# FilterSchematic_REV3.net
KiCad netlist of a schematic drawn in EAGLE
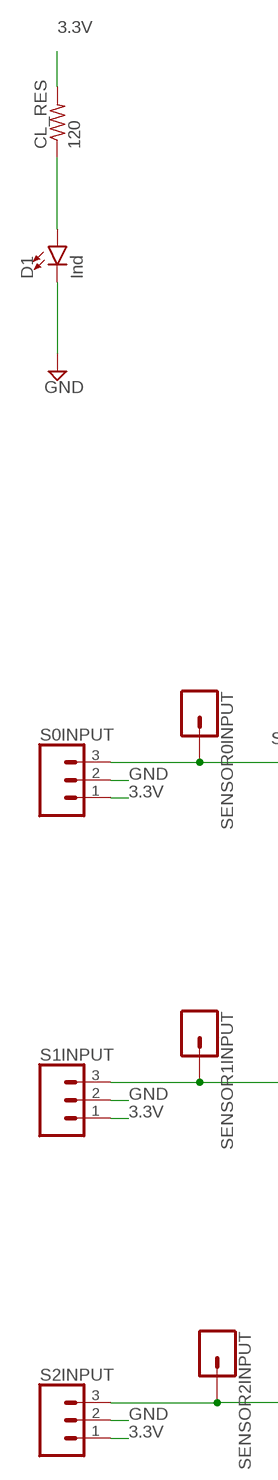
[diagram p0: schematic, sheet 1, part 1 of 2]
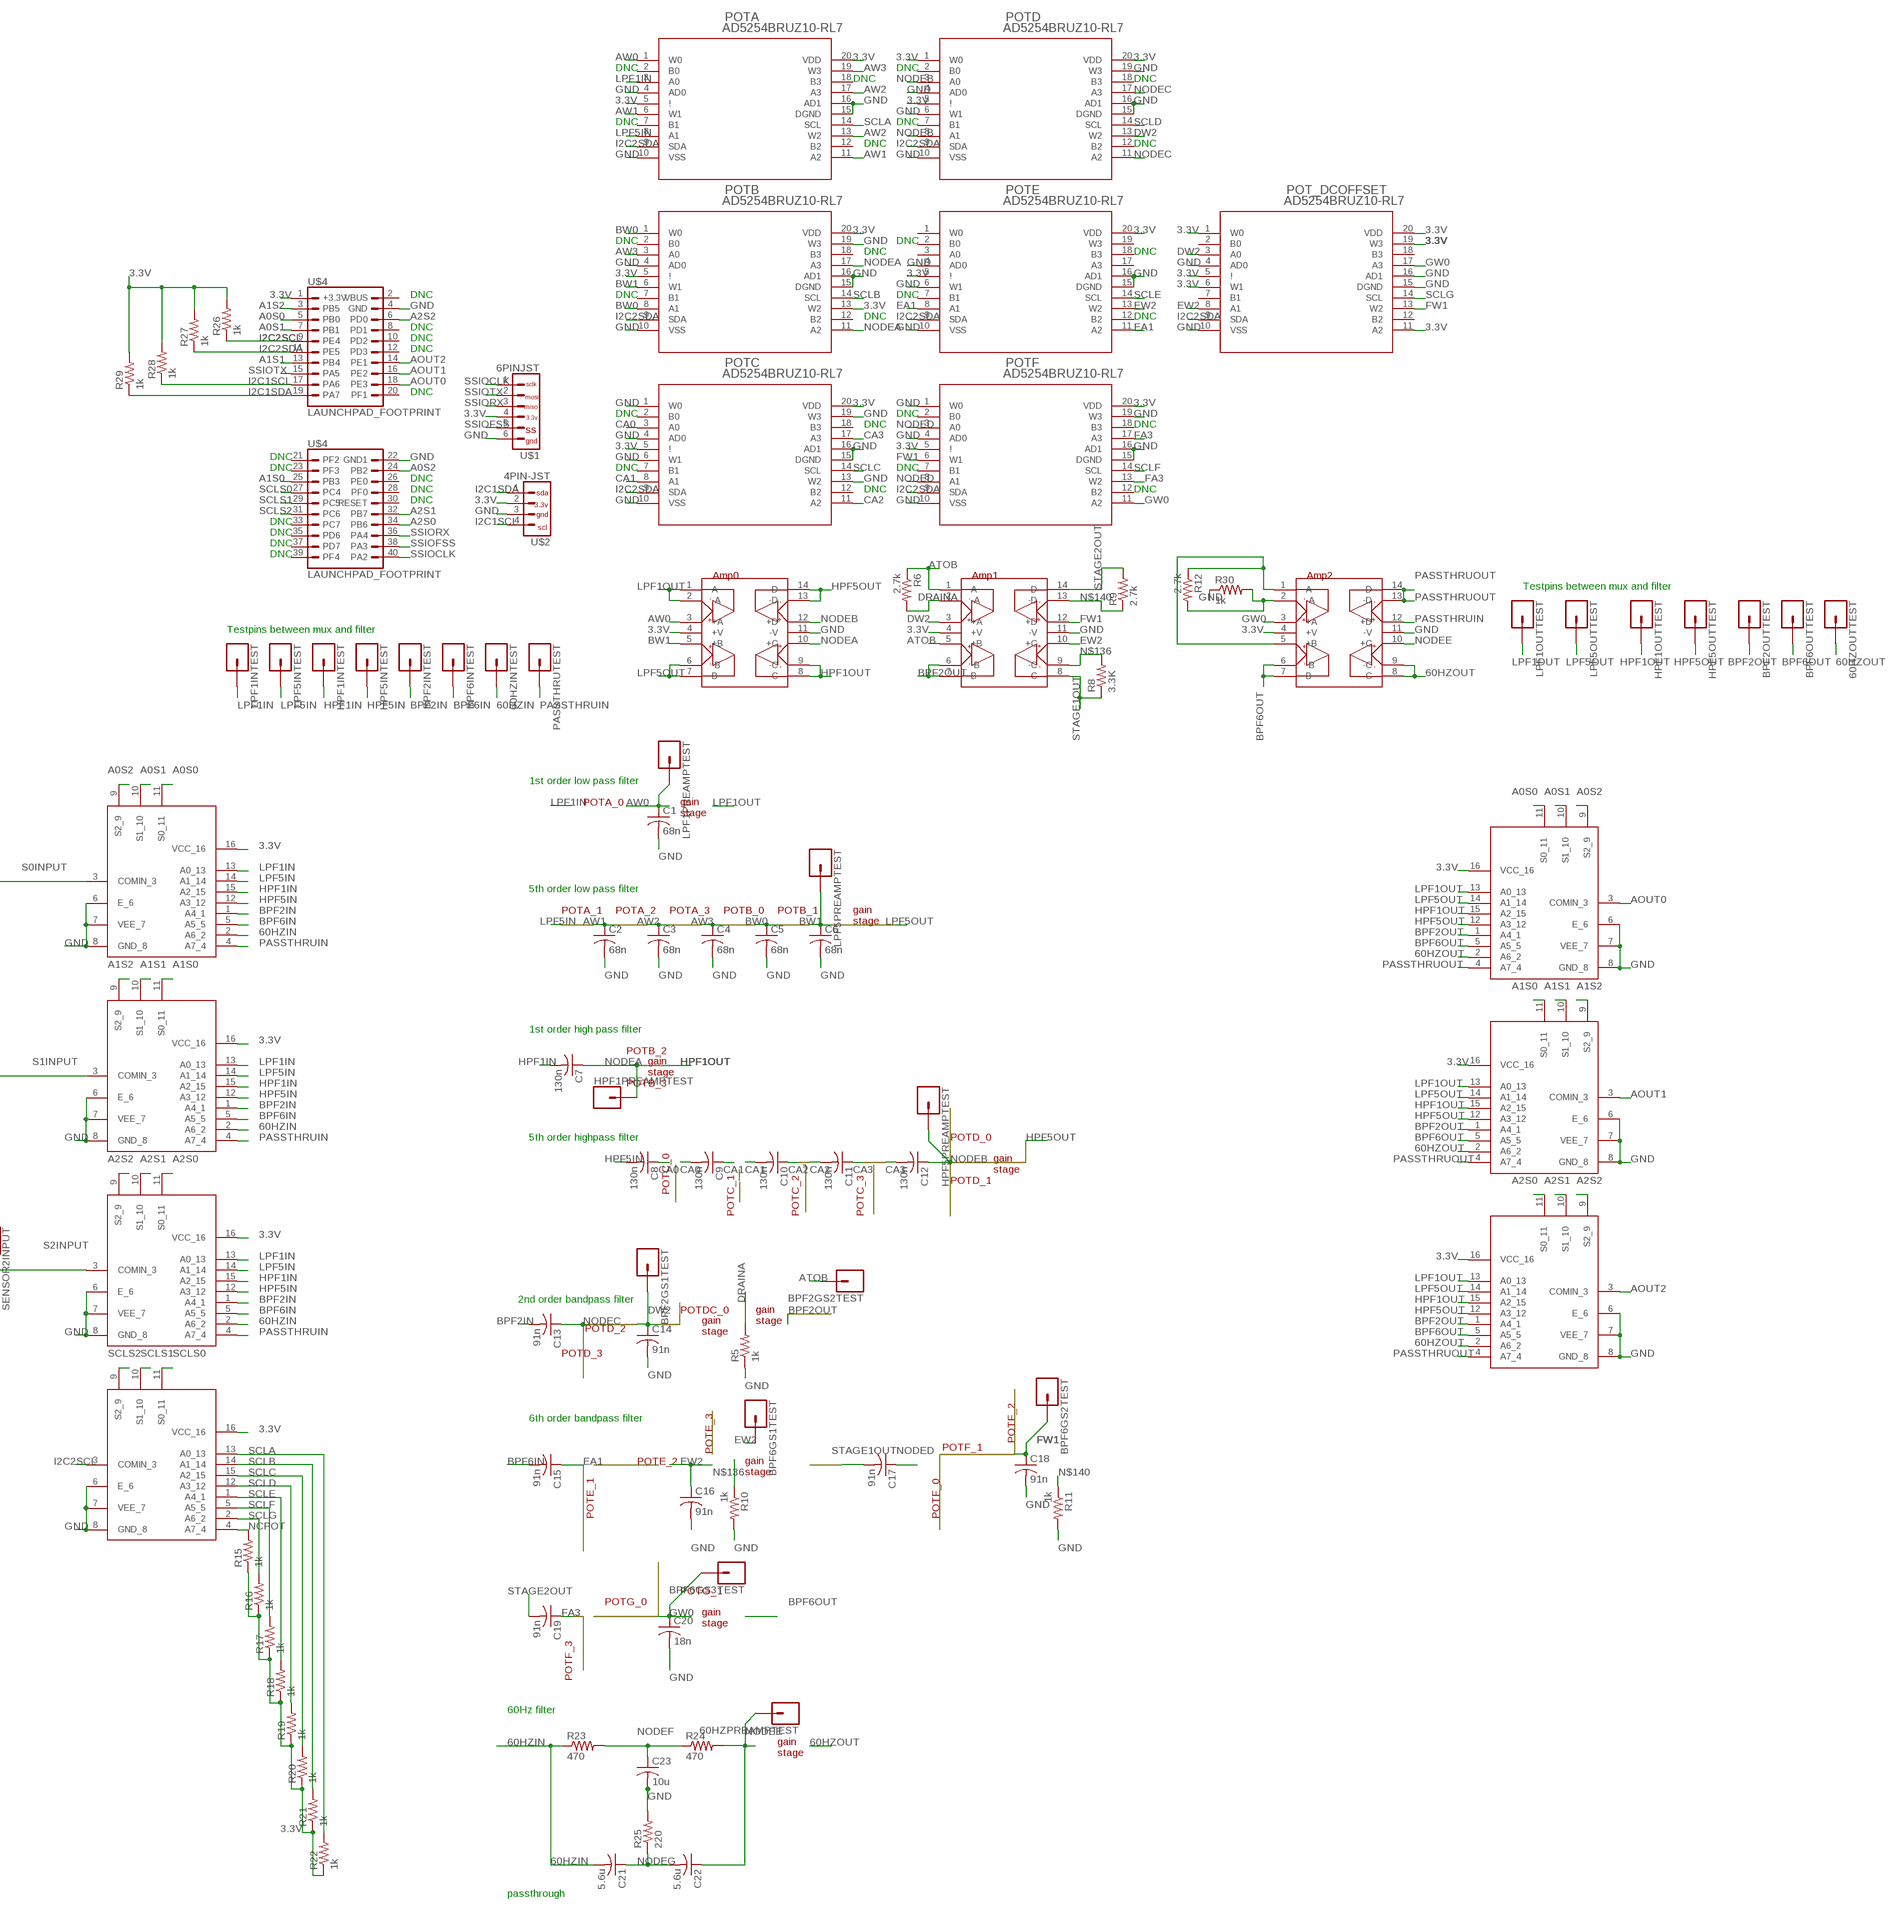
[diagram p1: schematic, sheet 1, part 2 of 2]

(export (version "E")
  (design (tool "Eeschema 10.0.6"))
  (components
    (comp (ref "60HZINTEST")
      (value "CONN_01")
      (footprint "eagle-import:1X01")
      (libsource (lib "eagle-import") (part "CONN_01"))
    )
    (comp (ref "60HZOUTTEST")
      (value "CONN_01")
      (footprint "eagle-import:1X01")
      (libsource (lib "eagle-import") (part "CONN_01"))
    )
    (comp (ref "60HZPREAMPTEST")
      (value "CONN_01")
      (footprint "eagle-import:1X01")
      (libsource (lib "eagle-import") (part "CONN_01"))
    )
    (comp (ref "A2IDEMUX")
      (value "CD74HC4051-Q1")
      (footprint "eagle-import:TSSOP16")
      (libsource (lib "eagle-import") (part "CD74HC4051-Q1"))
    )
    (comp (ref "AI0DEMUX")
      (value "CD74HC4051-Q1")
      (footprint "eagle-import:TSSOP16")
      (libsource (lib "eagle-import") (part "CD74HC4051-Q1"))
    )
    (comp (ref "AI1DEMUX")
      (value "CD74HC4051-Q1")
      (footprint "eagle-import:TSSOP16")
      (libsource (lib "eagle-import") (part "CD74HC4051-Q1"))
    )
    (comp (ref "AMP0")
      (value "OPA4830")
      (footprint "eagle-import:TSSOP14")
      (libsource (lib "eagle-import") (part "OPA4830"))
    )
    (comp (ref "AMP1")
      (value "OPA4830")
      (footprint "eagle-import:TSSOP14")
      (libsource (lib "eagle-import") (part "OPA4830"))
    )
    (comp (ref "AMP2")
      (value "OPA4830")
      (footprint "eagle-import:TSSOP14")
      (libsource (lib "eagle-import") (part "OPA4830"))
    )
    (comp (ref "AO0MUX")
      (value "CD74HC4051-Q1")
      (footprint "eagle-import:TSSOP16")
      (libsource (lib "eagle-import") (part "CD74HC4051-Q1"))
    )
    (comp (ref "AO1MUX")
      (value "CD74HC4051-Q1")
      (footprint "eagle-import:TSSOP16")
      (libsource (lib "eagle-import") (part "CD74HC4051-Q1"))
    )
    (comp (ref "AO2MUX")
      (value "CD74HC4051-Q1")
      (footprint "eagle-import:TSSOP16")
      (libsource (lib "eagle-import") (part "CD74HC4051-Q1"))
    )
    (comp (ref "BPF2GS1TEST")
      (value "CONN_01")
      (footprint "eagle-import:1X01")
      (libsource (lib "eagle-import") (part "CONN_01"))
    )
    (comp (ref "BPF2GS2TEST")
      (value "CONN_01")
      (footprint "eagle-import:1X01")
      (libsource (lib "eagle-import") (part "CONN_01"))
    )
    (comp (ref "BPF2INTEST")
      (value "CONN_01")
      (footprint "eagle-import:1X01")
      (libsource (lib "eagle-import") (part "CONN_01"))
    )
    (comp (ref "BPF2OUTTEST")
      (value "CONN_01")
      (footprint "eagle-import:1X01")
      (libsource (lib "eagle-import") (part "CONN_01"))
    )
    (comp (ref "BPF6GS1TEST")
      (value "CONN_01")
      (footprint "eagle-import:1X01")
      (libsource (lib "eagle-import") (part "CONN_01"))
    )
    (comp (ref "BPF6GS2TEST")
      (value "CONN_01")
      (footprint "eagle-import:1X01")
      (libsource (lib "eagle-import") (part "CONN_01"))
    )
    (comp (ref "BPF6GS3TEST")
      (value "CONN_01")
      (footprint "eagle-import:1X01")
      (libsource (lib "eagle-import") (part "CONN_01"))
    )
    (comp (ref "BPF6INTEST")
      (value "CONN_01")
      (footprint "eagle-import:1X01")
      (libsource (lib "eagle-import") (part "CONN_01"))
    )
    (comp (ref "BPF6OUTTEST")
      (value "CONN_01")
      (footprint "eagle-import:1X01")
      (libsource (lib "eagle-import") (part "CONN_01"))
    )
    (comp (ref "C1")
      (value "68n")
      (footprint "eagle-import:C0805")
      (libsource (lib "eagle-import") (part "C-USC0805"))
    )
    (comp (ref "C2")
      (value "68n")
      (footprint "eagle-import:C0805")
      (libsource (lib "eagle-import") (part "C-USC0805"))
    )
    (comp (ref "C3")
      (value "68n")
      (footprint "eagle-import:C0805")
      (libsource (lib "eagle-import") (part "C-USC0805"))
    )
    (comp (ref "C4")
      (value "68n")
      (footprint "eagle-import:C0805")
      (libsource (lib "eagle-import") (part "C-USC0805"))
    )
    (comp (ref "C5")
      (value "68n")
      (footprint "eagle-import:C0805")
      (libsource (lib "eagle-import") (part "C-USC0805"))
    )
    (comp (ref "C6")
      (value "68n")
      (footprint "eagle-import:C0805")
      (libsource (lib "eagle-import") (part "C-USC0805"))
    )
    (comp (ref "C7")
      (value "130n")
      (footprint "eagle-import:C0805")
      (libsource (lib "eagle-import") (part "C-USC0805"))
    )
    (comp (ref "C8")
      (value "130n")
      (footprint "eagle-import:C0805")
      (libsource (lib "eagle-import") (part "C-USC0805"))
    )
    (comp (ref "C9")
      (value "130n")
      (footprint "eagle-import:C0805")
      (libsource (lib "eagle-import") (part "C-USC0805"))
    )
    (comp (ref "C10")
      (value "130n")
      (footprint "eagle-import:C0805")
      (libsource (lib "eagle-import") (part "C-USC0805"))
    )
    (comp (ref "C11")
      (value "130n")
      (footprint "eagle-import:C0805")
      (libsource (lib "eagle-import") (part "C-USC0805"))
    )
    (comp (ref "C12")
      (value "130n")
      (footprint "eagle-import:C0805")
      (libsource (lib "eagle-import") (part "C-USC0805"))
    )
    (comp (ref "C13")
      (value "91n")
      (footprint "eagle-import:C0805")
      (libsource (lib "eagle-import") (part "C-USC0805"))
    )
    (comp (ref "C14")
      (value "91n")
      (footprint "eagle-import:C0805")
      (libsource (lib "eagle-import") (part "C-USC0805"))
    )
    (comp (ref "C15")
      (value "91n")
      (footprint "eagle-import:C0805")
      (libsource (lib "eagle-import") (part "C-USC0805"))
    )
    (comp (ref "C16")
      (value "91n")
      (footprint "eagle-import:C0805")
      (libsource (lib "eagle-import") (part "C-USC0805"))
    )
    (comp (ref "C17")
      (value "91n")
      (footprint "eagle-import:C0805")
      (libsource (lib "eagle-import") (part "C-USC0805"))
    )
    (comp (ref "C18")
      (value "91n")
      (footprint "eagle-import:C0805")
      (libsource (lib "eagle-import") (part "C-USC0805"))
    )
    (comp (ref "C19")
      (value "91n")
      (footprint "eagle-import:C0805")
      (libsource (lib "eagle-import") (part "C-USC0805"))
    )
    (comp (ref "C20")
      (value "18n")
      (footprint "eagle-import:C0805")
      (libsource (lib "eagle-import") (part "C-USC0805"))
    )
    (comp (ref "C21")
      (value "5.6u")
      (footprint "eagle-import:C0805")
      (libsource (lib "eagle-import") (part "C-USC0805"))
    )
    (comp (ref "C22")
      (value "5.6u")
      (footprint "eagle-import:C0805")
      (libsource (lib "eagle-import") (part "C-USC0805"))
    )
    (comp (ref "C23")
      (value "10u")
      (footprint "eagle-import:C0805")
      (libsource (lib "eagle-import") (part "C-USC0805"))
    )
    (comp (ref "CL_RES")
      (value "120")
      (footprint "eagle-import:R0805")
      (libsource (lib "eagle-import") (part "rcl_334_R-US_R0805"))
    )
    (comp (ref "D1")
      (value "Ind")
      (footprint "eagle-import:LED-0603")
      (libsource (lib "eagle-import") (part "LED-GREEN0603"))
    )
    (comp (ref "HPF1INTEST")
      (value "CONN_01")
      (footprint "eagle-import:1X01")
      (libsource (lib "eagle-import") (part "CONN_01"))
    )
    (comp (ref "HPF1OUTTEST")
      (value "CONN_01")
      (footprint "eagle-import:1X01")
      (libsource (lib "eagle-import") (part "CONN_01"))
    )
    (comp (ref "HPF1PREAMPTEST")
      (value "CONN_01")
      (footprint "eagle-import:1X01")
      (libsource (lib "eagle-import") (part "CONN_01"))
    )
    (comp (ref "HPF5INTEST")
      (value "CONN_01")
      (footprint "eagle-import:1X01")
      (libsource (lib "eagle-import") (part "CONN_01"))
    )
    (comp (ref "HPF5OUTTEST")
      (value "CONN_01")
      (footprint "eagle-import:1X01")
      (libsource (lib "eagle-import") (part "CONN_01"))
    )
    (comp (ref "HPF5PREAMPTEST")
      (value "CONN_01")
      (footprint "eagle-import:1X01")
      (libsource (lib "eagle-import") (part "CONN_01"))
    )
    (comp (ref "LPF1INTEST")
      (value "CONN_01")
      (footprint "eagle-import:1X01")
      (libsource (lib "eagle-import") (part "CONN_01"))
    )
    (comp (ref "LPF1OUTTEST")
      (value "CONN_01")
      (footprint "eagle-import:1X01")
      (libsource (lib "eagle-import") (part "CONN_01"))
    )
    (comp (ref "LPF1PREAMPTEST")
      (value "CONN_01")
      (footprint "eagle-import:1X01")
      (libsource (lib "eagle-import") (part "CONN_01"))
    )
    (comp (ref "LPF5INTEST")
      (value "CONN_01")
      (footprint "eagle-import:1X01")
      (libsource (lib "eagle-import") (part "CONN_01"))
    )
    (comp (ref "LPF5OUTTEST")
      (value "CONN_01")
      (footprint "eagle-import:1X01")
      (libsource (lib "eagle-import") (part "CONN_01"))
    )
    (comp (ref "LPF5PREAMPTEST")
      (value "CONN_01")
      (footprint "eagle-import:1X01")
      (libsource (lib "eagle-import") (part "CONN_01"))
    )
    (comp (ref "PASSTHRUTEST")
      (value "CONN_01")
      (footprint "eagle-import:1X01")
      (libsource (lib "eagle-import") (part "CONN_01"))
    )
    (comp (ref "POTA")
      (value "AD5254BRUZ10-RL7")
      (footprint "eagle-import:RU_20")
      (fields (field (name "MANUFACTURER_PART_NUMBER") "AD5254BRUZ10RL7"))
      (libsource (lib "eagle-import") (part "AD5254BRUZ10-RL7"))
    )
    (comp (ref "POTB")
      (value "AD5254BRUZ10-RL7")
      (footprint "eagle-import:RU_20")
      (fields (field (name "MANUFACTURER_PART_NUMBER") "AD5254BRUZ10RL7"))
      (libsource (lib "eagle-import") (part "AD5254BRUZ10-RL7"))
    )
    (comp (ref "POTC")
      (value "AD5254BRUZ10-RL7")
      (footprint "eagle-import:RU_20")
      (fields (field (name "MANUFACTURER_PART_NUMBER") "AD5254BRUZ10RL7"))
      (libsource (lib "eagle-import") (part "AD5254BRUZ10-RL7"))
    )
    (comp (ref "POTD")
      (value "AD5254BRUZ10-RL7")
      (footprint "eagle-import:RU_20")
      (fields (field (name "MANUFACTURER_PART_NUMBER") "AD5254BRUZ10RL7"))
      (libsource (lib "eagle-import") (part "AD5254BRUZ10-RL7"))
    )
    (comp (ref "POTE")
      (value "AD5254BRUZ10-RL7")
      (footprint "eagle-import:RU_20")
      (fields (field (name "MANUFACTURER_PART_NUMBER") "AD5254BRUZ10RL7"))
      (libsource (lib "eagle-import") (part "AD5254BRUZ10-RL7"))
    )
    (comp (ref "POTF")
      (value "AD5254BRUZ10-RL7")
      (footprint "eagle-import:RU_20")
      (fields (field (name "MANUFACTURER_PART_NUMBER") "AD5254BRUZ10RL7"))
      (libsource (lib "eagle-import") (part "AD5254BRUZ10-RL7"))
    )
    (comp (ref "POT_DCOFFSET")
      (value "AD5254BRUZ10-RL7")
      (footprint "eagle-import:RU_20")
      (fields (field (name "MANUFACTURER_PART_NUMBER") "AD5254BRUZ10RL7"))
      (libsource (lib "eagle-import") (part "AD5254BRUZ10-RL7"))
    )
    (comp (ref "R5")
      (value "1k")
      (footprint "eagle-import:R0805")
      (libsource (lib "eagle-import") (part "rcl_334_R-US_R0805"))
    )
    (comp (ref "R6")
      (value "2.7k")
      (footprint "eagle-import:R0805")
      (libsource (lib "eagle-import") (part "rcl_334_R-US_R0805"))
    )
    (comp (ref "R8")
      (value "3.3K")
      (footprint "eagle-import:R0805")
      (libsource (lib "eagle-import") (part "rcl_334_R-US_R0805"))
    )
    (comp (ref "R9")
      (value "2.7k")
      (footprint "eagle-import:R0805")
      (libsource (lib "eagle-import") (part "rcl_334_R-US_R0805"))
    )
    (comp (ref "R10")
      (value "1k")
      (footprint "eagle-import:R0805")
      (libsource (lib "eagle-import") (part "rcl_334_R-US_R0805"))
    )
    (comp (ref "R11")
      (value "1k")
      (footprint "eagle-import:R0805")
      (libsource (lib "eagle-import") (part "rcl_334_R-US_R0805"))
    )
    (comp (ref "R12")
      (value "2.7k")
      (footprint "eagle-import:R0805")
      (libsource (lib "eagle-import") (part "rcl_334_R-US_R0805"))
    )
    (comp (ref "R15")
      (value "1k")
      (footprint "eagle-import:R0805")
      (libsource (lib "eagle-import") (part "rcl_334_R-US_R0805"))
    )
    (comp (ref "R16")
      (value "1k")
      (footprint "eagle-import:R0805")
      (libsource (lib "eagle-import") (part "rcl_334_R-US_R0805"))
    )
    (comp (ref "R17")
      (value "1k")
      (footprint "eagle-import:R0805")
      (libsource (lib "eagle-import") (part "rcl_334_R-US_R0805"))
    )
    (comp (ref "R18")
      (value "1k")
      (footprint "eagle-import:R0805")
      (libsource (lib "eagle-import") (part "rcl_334_R-US_R0805"))
    )
    (comp (ref "R19")
      (value "1k")
      (footprint "eagle-import:R0805")
      (libsource (lib "eagle-import") (part "rcl_334_R-US_R0805"))
    )
    (comp (ref "R20")
      (value "1k")
      (footprint "eagle-import:R0805")
      (libsource (lib "eagle-import") (part "rcl_334_R-US_R0805"))
    )
    (comp (ref "R21")
      (value "1k")
      (footprint "eagle-import:R0805")
      (libsource (lib "eagle-import") (part "rcl_334_R-US_R0805"))
    )
    (comp (ref "R22")
      (value "1k")
      (footprint "eagle-import:R0805")
      (libsource (lib "eagle-import") (part "rcl_334_R-US_R0805"))
    )
    (comp (ref "R23")
      (value "470")
      (footprint "eagle-import:R0805")
      (libsource (lib "eagle-import") (part "R-US_R0805"))
    )
    (comp (ref "R24")
      (value "470")
      (footprint "eagle-import:R0805")
      (libsource (lib "eagle-import") (part "R-US_R0805"))
    )
    (comp (ref "R25")
      (value "220")
      (footprint "eagle-import:R0805")
      (libsource (lib "eagle-import") (part "R-US_R0805"))
    )
    (comp (ref "R26")
      (value "1k")
      (footprint "eagle-import:R0805")
      (libsource (lib "eagle-import") (part "rcl_334_R-US_R0805"))
    )
    (comp (ref "R27")
      (value "1k")
      (footprint "eagle-import:R0805")
      (libsource (lib "eagle-import") (part "rcl_334_R-US_R0805"))
    )
    (comp (ref "R28")
      (value "1k")
      (footprint "eagle-import:R0805")
      (libsource (lib "eagle-import") (part "rcl_334_R-US_R0805"))
    )
    (comp (ref "R29")
      (value "1k")
      (footprint "eagle-import:R0805")
      (libsource (lib "eagle-import") (part "rcl_334_R-US_R0805"))
    )
    (comp (ref "R30")
      (value "1k")
      (footprint "eagle-import:R0805")
      (libsource (lib "eagle-import") (part "rcl_334_R-US_R0805"))
    )
    (comp (ref "S0INPUT")
      (value "CONN_03JST-PTH-VERT")
      (footprint "eagle-import:JST-3-PTH-VERT")
      (libsource (lib "eagle-import") (part "CONN_03JST-PTH-VERT"))
    )
    (comp (ref "S1INPUT")
      (value "CONN_03JST-PTH-VERT")
      (footprint "eagle-import:JST-3-PTH-VERT")
      (libsource (lib "eagle-import") (part "CONN_03JST-PTH-VERT"))
    )
    (comp (ref "S2INPUT")
      (value "CONN_03JST-PTH-VERT")
      (footprint "eagle-import:JST-3-PTH-VERT")
      (libsource (lib "eagle-import") (part "CONN_03JST-PTH-VERT"))
    )
    (comp (ref "SCLMUX")
      (value "CD74HC4051-Q1")
      (footprint "eagle-import:TSSOP16")
      (libsource (lib "eagle-import") (part "CD74HC4051-Q1"))
    )
    (comp (ref "SENSOR0INPUT")
      (value "CONN_01")
      (footprint "eagle-import:1X01")
      (libsource (lib "eagle-import") (part "CONN_01"))
    )
    (comp (ref "SENSOR1INPUT")
      (value "CONN_01")
      (footprint "eagle-import:1X01")
      (libsource (lib "eagle-import") (part "CONN_01"))
    )
    (comp (ref "SENSOR2INPUT")
      (value "CONN_01")
      (footprint "eagle-import:1X01")
      (libsource (lib "eagle-import") (part "CONN_01"))
    )
    (comp (ref "U$1")
      (value "6PINJST")
      (footprint "eagle-import:JST-6-PTH-VERT")
      (libsource (lib "eagle-import") (part "6PINJST"))
    )
    (comp (ref "U$2")
      (value "4PIN-JST")
      (footprint "eagle-import:JST-4-PTH-VERT")
      (libsource (lib "eagle-import") (part "4PIN-JST"))
    )
    (comp (ref "U$4")
      (value "LAUNCHPAD_FOOTPRINT")
      (footprint "eagle-import:SSW-110-02-S-D")
      (libsource (lib "eagle-import") (part "LAUNCHPAD_FOOTPRINT"))
    )
  )
  (nets
    (net (code "1") (name "/3.3V") (class "Default")
      (node (ref "A2IDEMUX") (pin "16") (pinfunction "VCC_16_16") (pintype "bidirectional"))
      (node (ref "AI0DEMUX") (pin "16") (pinfunction "VCC_16_16") (pintype "bidirectional"))
      (node (ref "AI1DEMUX") (pin "16") (pinfunction "VCC_16_16") (pintype "bidirectional"))
      (node (ref "AMP0") (pin "4") (pinfunction "+V_4") (pintype "bidirectional"))
      (node (ref "AMP1") (pin "4") (pinfunction "+V_4") (pintype "bidirectional"))
      (node (ref "AMP2") (pin "4") (pinfunction "+V_4") (pintype "bidirectional"))
      (node (ref "AO0MUX") (pin "16") (pinfunction "VCC_16_16") (pintype "bidirectional"))
      (node (ref "AO1MUX") (pin "16") (pinfunction "VCC_16_16") (pintype "bidirectional"))
      (node (ref "AO2MUX") (pin "16") (pinfunction "VCC_16_16") (pintype "bidirectional"))
      (node (ref "CL_RES") (pin "2") (pinfunction "2_2") (pintype "passive"))
      (node (ref "POTA") (pin "20") (pinfunction "VDD_20") (pintype "power_in"))
      (node (ref "POTA") (pin "5") (pinfunction "~_5") (pintype "passive"))
      (node (ref "POTB") (pin "13") (pinfunction "W2_13") (pintype "passive"))
      (node (ref "POTB") (pin "20") (pinfunction "VDD_20") (pintype "power_in"))
      (node (ref "POTB") (pin "5") (pinfunction "~_5") (pintype "passive"))
      (node (ref "POTC") (pin "20") (pinfunction "VDD_20") (pintype "power_in"))
      (node (ref "POTC") (pin "5") (pinfunction "~_5") (pintype "passive"))
      (node (ref "POTD") (pin "1") (pinfunction "W0_1") (pintype "passive"))
      (node (ref "POTD") (pin "20") (pinfunction "VDD_20") (pintype "power_in"))
      (node (ref "POTD") (pin "5") (pinfunction "~_5") (pintype "passive"))
      (node (ref "POTE") (pin "20") (pinfunction "VDD_20") (pintype "power_in"))
      (node (ref "POTE") (pin "5") (pinfunction "~_5") (pintype "passive"))
      (node (ref "POTF") (pin "20") (pinfunction "VDD_20") (pintype "power_in"))
      (node (ref "POTF") (pin "5") (pinfunction "~_5") (pintype "passive"))
      (node (ref "POT_DCOFFSET") (pin "1") (pinfunction "W0_1") (pintype "passive"))
      (node (ref "POT_DCOFFSET") (pin "11") (pinfunction "A2_11") (pintype "passive"))
      (node (ref "POT_DCOFFSET") (pin "19") (pinfunction "W3_19") (pintype "passive"))
      (node (ref "POT_DCOFFSET") (pin "20") (pinfunction "VDD_20") (pintype "power_in"))
      (node (ref "POT_DCOFFSET") (pin "5") (pinfunction "~_5") (pintype "passive"))
      (node (ref "POT_DCOFFSET") (pin "6") (pinfunction "W1_6") (pintype "passive"))
      (node (ref "R15") (pin "1") (pinfunction "1_1") (pintype "passive"))
      (node (ref "R16") (pin "1") (pinfunction "1_1") (pintype "passive"))
      (node (ref "R17") (pin "1") (pinfunction "1_1") (pintype "passive"))
      (node (ref "R18") (pin "1") (pinfunction "1_1") (pintype "passive"))
      (node (ref "R19") (pin "1") (pinfunction "1_1") (pintype "passive"))
      (node (ref "R20") (pin "1") (pinfunction "1_1") (pintype "passive"))
      (node (ref "R21") (pin "1") (pinfunction "1_1") (pintype "passive"))
      (node (ref "R22") (pin "1") (pinfunction "1_1") (pintype "passive"))
      (node (ref "R26") (pin "2") (pinfunction "2_2") (pintype "passive"))
      (node (ref "R27") (pin "2") (pinfunction "2_2") (pintype "passive"))
      (node (ref "R28") (pin "2") (pinfunction "2_2") (pintype "passive"))
      (node (ref "R29") (pin "2") (pinfunction "2_2") (pintype "passive"))
      (node (ref "S0INPUT") (pin "1") (pinfunction "1_1") (pintype "passive"))
      (node (ref "S1INPUT") (pin "1") (pinfunction "1_1") (pintype "passive"))
      (node (ref "S2INPUT") (pin "1") (pinfunction "1_1") (pintype "passive"))
      (node (ref "SCLMUX") (pin "16") (pinfunction "VCC_16_16") (pintype "bidirectional"))
      (node (ref "U$1") (pin "4") (pinfunction "4_4") (pintype "passive"))
      (node (ref "U$2") (pin "2") (pinfunction "2_2") (pintype "passive"))
      (node (ref "U$4") (pin "1") (pinfunction "+3.3V_1") (pintype "passive"))
    )
    (net (code "2") (name "/60HZIN") (class "Default")
      (node (ref "60HZINTEST") (pin "1") (pinfunction "1_1") (pintype "passive"))
      (node (ref "A2IDEMUX") (pin "2") (pinfunction "A6_2_2") (pintype "bidirectional"))
      (node (ref "AI0DEMUX") (pin "2") (pinfunction "A6_2_2") (pintype "bidirectional"))
      (node (ref "AI1DEMUX") (pin "2") (pinfunction "A6_2_2") (pintype "bidirectional"))
      (node (ref "C21") (pin "2") (pinfunction "2_2") (pintype "passive"))
      (node (ref "R23") (pin "1") (pinfunction "1_1") (pintype "passive"))
    )
    (net (code "3") (name "/60HZOUT") (class "Default")
      (node (ref "60HZOUTTEST") (pin "1") (pinfunction "1_1") (pintype "passive"))
      (node (ref "AMP2") (pin "8") (pinfunction "C_8") (pintype "bidirectional"))
      (node (ref "AMP2") (pin "9") (pinfunction "-C_9") (pintype "bidirectional"))
      (node (ref "AO0MUX") (pin "2") (pinfunction "A6_2_2") (pintype "bidirectional"))
      (node (ref "AO1MUX") (pin "2") (pinfunction "A6_2_2") (pintype "bidirectional"))
      (node (ref "AO2MUX") (pin "2") (pinfunction "A6_2_2") (pintype "bidirectional"))
    )
    (net (code "4") (name "/A0S0") (class "Default")
      (node (ref "AI0DEMUX") (pin "11") (pinfunction "S0_11_11") (pintype "bidirectional"))
      (node (ref "AO0MUX") (pin "11") (pinfunction "S0_11_11") (pintype "bidirectional"))
      (node (ref "U$4") (pin "5") (pinfunction "PB0_5") (pintype "passive"))
    )
    (net (code "5") (name "/A0S1") (class "Default")
      (node (ref "AI0DEMUX") (pin "10") (pinfunction "S1_10_10") (pintype "bidirectional"))
      (node (ref "AO0MUX") (pin "10") (pinfunction "S1_10_10") (pintype "bidirectional"))
      (node (ref "U$4") (pin "7") (pinfunction "PB1_7") (pintype "passive"))
    )
    (net (code "6") (name "/A0S2") (class "Default")
      (node (ref "AI0DEMUX") (pin "9") (pinfunction "S2_9_9") (pintype "bidirectional"))
      (node (ref "AO0MUX") (pin "9") (pinfunction "S2_9_9") (pintype "bidirectional"))
      (node (ref "U$4") (pin "24") (pinfunction "PB2_24") (pintype "passive"))
    )
    (net (code "7") (name "/A1S0") (class "Default")
      (node (ref "AI1DEMUX") (pin "11") (pinfunction "S0_11_11") (pintype "bidirectional"))
      (node (ref "AO1MUX") (pin "11") (pinfunction "S0_11_11") (pintype "bidirectional"))
      (node (ref "U$4") (pin "25") (pinfunction "PB3_25") (pintype "passive"))
    )
    (net (code "8") (name "/A1S1") (class "Default")
      (node (ref "AI1DEMUX") (pin "10") (pinfunction "S1_10_10") (pintype "bidirectional"))
      (node (ref "AO1MUX") (pin "10") (pinfunction "S1_10_10") (pintype "bidirectional"))
      (node (ref "U$4") (pin "13") (pinfunction "PB4_13") (pintype "passive"))
    )
    (net (code "9") (name "/A1S2") (class "Default")
      (node (ref "AI1DEMUX") (pin "9") (pinfunction "S2_9_9") (pintype "bidirectional"))
      (node (ref "AO1MUX") (pin "9") (pinfunction "S2_9_9") (pintype "bidirectional"))
      (node (ref "U$4") (pin "3") (pinfunction "PB5_3") (pintype "passive"))
    )
    (net (code "10") (name "/A2S0") (class "Default")
      (node (ref "A2IDEMUX") (pin "11") (pinfunction "S0_11_11") (pintype "bidirectional"))
      (node (ref "AO2MUX") (pin "11") (pinfunction "S0_11_11") (pintype "bidirectional"))
      (node (ref "U$4") (pin "34") (pinfunction "PB6_34") (pintype "passive"))
    )
    (net (code "11") (name "/A2S1") (class "Default")
      (node (ref "A2IDEMUX") (pin "10") (pinfunction "S1_10_10") (pintype "bidirectional"))
      (node (ref "AO2MUX") (pin "10") (pinfunction "S1_10_10") (pintype "bidirectional"))
      (node (ref "U$4") (pin "32") (pinfunction "PB7_32") (pintype "passive"))
    )
    (net (code "12") (name "/A2S2") (class "Default")
      (node (ref "A2IDEMUX") (pin "9") (pinfunction "S2_9_9") (pintype "bidirectional"))
      (node (ref "AO2MUX") (pin "9") (pinfunction "S2_9_9") (pintype "bidirectional"))
      (node (ref "U$4") (pin "6") (pinfunction "PD0_6") (pintype "passive"))
    )
    (net (code "13") (name "/AOUT0") (class "Default")
      (node (ref "AO0MUX") (pin "3") (pinfunction "COMIN_3_3") (pintype "bidirectional"))
      (node (ref "U$4") (pin "18") (pinfunction "PE3_18") (pintype "passive"))
    )
    (net (code "14") (name "/AOUT1") (class "Default")
      (node (ref "AO1MUX") (pin "3") (pinfunction "COMIN_3_3") (pintype "bidirectional"))
      (node (ref "U$4") (pin "16") (pinfunction "PE2_16") (pintype "passive"))
    )
    (net (code "15") (name "/AOUT2") (class "Default")
      (node (ref "AO2MUX") (pin "3") (pinfunction "COMIN_3_3") (pintype "bidirectional"))
      (node (ref "U$4") (pin "14") (pinfunction "PE1_14") (pintype "passive"))
    )
    (net (code "16") (name "/ATOB") (class "Default")
      (node (ref "AMP1") (pin "1") (pinfunction "A_1") (pintype "bidirectional"))
      (node (ref "AMP1") (pin "5") (pinfunction "+B_5") (pintype "bidirectional"))
      (node (ref "BPF2GS2TEST") (pin "1") (pinfunction "1_1") (pintype "passive"))
      (node (ref "R6") (pin "1") (pinfunction "1_1") (pintype "passive"))
    )
    (net (code "17") (name "/AW0") (class "Default")
      (node (ref "AMP0") (pin "3") (pinfunction "+A_3") (pintype "bidirectional"))
      (node (ref "C1") (pin "1") (pinfunction "1_1") (pintype "passive"))
      (node (ref "LPF1PREAMPTEST") (pin "1") (pinfunction "1_1") (pintype "passive"))
      (node (ref "POTA") (pin "1") (pinfunction "W0_1") (pintype "passive"))
    )
    (net (code "18") (name "/AW1") (class "Default")
      (node (ref "C2") (pin "1") (pinfunction "1_1") (pintype "passive"))
      (node (ref "POTA") (pin "11") (pinfunction "A2_11") (pintype "passive"))
      (node (ref "POTA") (pin "6") (pinfunction "W1_6") (pintype "passive"))
    )
    (net (code "19") (name "/AW2") (class "Default")
      (node (ref "C3") (pin "1") (pinfunction "1_1") (pintype "passive"))
      (node (ref "POTA") (pin "13") (pinfunction "W2_13") (pintype "passive"))
      (node (ref "POTA") (pin "17") (pinfunction "A3_17") (pintype "passive"))
    )
    (net (code "20") (name "/AW3") (class "Default")
      (node (ref "C4") (pin "1") (pinfunction "1_1") (pintype "passive"))
      (node (ref "POTA") (pin "19") (pinfunction "W3_19") (pintype "passive"))
      (node (ref "POTB") (pin "3") (pinfunction "A0_3") (pintype "passive"))
    )
    (net (code "21") (name "/BPF2IN") (class "Default")
      (node (ref "A2IDEMUX") (pin "1") (pinfunction "A4_1_1") (pintype "bidirectional"))
      (node (ref "AI0DEMUX") (pin "1") (pinfunction "A4_1_1") (pintype "bidirectional"))
      (node (ref "AI1DEMUX") (pin "1") (pinfunction "A4_1_1") (pintype "bidirectional"))
      (node (ref "BPF2INTEST") (pin "1") (pinfunction "1_1") (pintype "passive"))
      (node (ref "C13") (pin "2") (pinfunction "2_2") (pintype "passive"))
    )
    (net (code "22") (name "/BPF2OUT") (class "Default")
      (node (ref "AMP1") (pin "6") (pinfunction "-B_6") (pintype "bidirectional"))
      (node (ref "AMP1") (pin "7") (pinfunction "B_7") (pintype "bidirectional"))
      (node (ref "AO0MUX") (pin "1") (pinfunction "A4_1_1") (pintype "bidirectional"))
      (node (ref "AO1MUX") (pin "1") (pinfunction "A4_1_1") (pintype "bidirectional"))
      (node (ref "AO2MUX") (pin "1") (pinfunction "A4_1_1") (pintype "bidirectional"))
      (node (ref "BPF2OUTTEST") (pin "1") (pinfunction "1_1") (pintype "passive"))
    )
    (net (code "23") (name "/BPF6IN") (class "Default")
      (node (ref "A2IDEMUX") (pin "5") (pinfunction "A5_5_5") (pintype "bidirectional"))
      (node (ref "AI0DEMUX") (pin "5") (pinfunction "A5_5_5") (pintype "bidirectional"))
      (node (ref "AI1DEMUX") (pin "5") (pinfunction "A5_5_5") (pintype "bidirectional"))
      (node (ref "BPF6INTEST") (pin "1") (pinfunction "1_1") (pintype "passive"))
      (node (ref "C15") (pin "2") (pinfunction "2_2") (pintype "passive"))
    )
    (net (code "24") (name "/BPF6OUT") (class "Default")
      (node (ref "AMP2") (pin "6") (pinfunction "-B_6") (pintype "bidirectional"))
      (node (ref "AMP2") (pin "7") (pinfunction "B_7") (pintype "bidirectional"))
      (node (ref "AO0MUX") (pin "5") (pinfunction "A5_5_5") (pintype "bidirectional"))
      (node (ref "AO1MUX") (pin "5") (pinfunction "A5_5_5") (pintype "bidirectional"))
      (node (ref "AO2MUX") (pin "5") (pinfunction "A5_5_5") (pintype "bidirectional"))
      (node (ref "BPF6OUTTEST") (pin "1") (pinfunction "1_1") (pintype "passive"))
    )
    (net (code "25") (name "/BW0") (class "Default")
      (node (ref "C5") (pin "1") (pinfunction "1_1") (pintype "passive"))
      (node (ref "POTB") (pin "1") (pinfunction "W0_1") (pintype "passive"))
      (node (ref "POTB") (pin "8") (pinfunction "A1_8") (pintype "passive"))
    )
    (net (code "26") (name "/BW1") (class "Default")
      (node (ref "AMP0") (pin "5") (pinfunction "+B_5") (pintype "bidirectional"))
      (node (ref "C6") (pin "1") (pinfunction "1_1") (pintype "passive"))
      (node (ref "LPF5PREAMPTEST") (pin "1") (pinfunction "1_1") (pintype "passive"))
      (node (ref "POTB") (pin "6") (pinfunction "W1_6") (pintype "passive"))
    )
    (net (code "27") (name "/CA0") (class "Default")
      (node (ref "C8") (pin "1") (pinfunction "1_1") (pintype "passive"))
      (node (ref "C9") (pin "2") (pinfunction "2_2") (pintype "passive"))
      (node (ref "POTC") (pin "3") (pinfunction "A0_3") (pintype "passive"))
    )
    (net (code "28") (name "/CA1") (class "Default")
      (node (ref "C10") (pin "2") (pinfunction "2_2") (pintype "passive"))
      (node (ref "C9") (pin "1") (pinfunction "1_1") (pintype "passive"))
      (node (ref "POTC") (pin "8") (pinfunction "A1_8") (pintype "passive"))
    )
    (net (code "29") (name "/CA2") (class "Default")
      (node (ref "C10") (pin "1") (pinfunction "1_1") (pintype "passive"))
      (node (ref "C11") (pin "2") (pinfunction "2_2") (pintype "passive"))
      (node (ref "POTC") (pin "11") (pinfunction "A2_11") (pintype "passive"))
    )
    (net (code "30") (name "/CA3") (class "Default")
      (node (ref "C11") (pin "1") (pinfunction "1_1") (pintype "passive"))
      (node (ref "C12") (pin "2") (pinfunction "2_2") (pintype "passive"))
      (node (ref "POTC") (pin "17") (pinfunction "A3_17") (pintype "passive"))
    )
    (net (code "31") (name "/DRAINA") (class "Default")
      (node (ref "AMP1") (pin "2") (pinfunction "-A_2") (pintype "bidirectional"))
      (node (ref "R5") (pin "2") (pinfunction "2_2") (pintype "passive"))
      (node (ref "R6") (pin "2") (pinfunction "2_2") (pintype "passive"))
    )
    (net (code "32") (name "/DW2") (class "Default")
      (node (ref "AMP1") (pin "3") (pinfunction "+A_3") (pintype "bidirectional"))
      (node (ref "BPF2GS1TEST") (pin "1") (pinfunction "1_1") (pintype "passive"))
      (node (ref "C14") (pin "1") (pinfunction "1_1") (pintype "passive"))
      (node (ref "POTD") (pin "13") (pinfunction "W2_13") (pintype "passive"))
      (node (ref "POT_DCOFFSET") (pin "3") (pinfunction "A0_3") (pintype "passive"))
    )
    (net (code "33") (name "/EA1") (class "Default")
      (node (ref "C15") (pin "1") (pinfunction "1_1") (pintype "passive"))
      (node (ref "POTE") (pin "11") (pinfunction "A2_11") (pintype "passive"))
      (node (ref "POTE") (pin "8") (pinfunction "A1_8") (pintype "passive"))
    )
    (net (code "34") (name "/EW2") (class "Default")
      (node (ref "AMP1") (pin "10") (pinfunction "+C_10") (pintype "bidirectional"))
      (node (ref "BPF6GS1TEST") (pin "1") (pinfunction "1_1") (pintype "passive"))
      (node (ref "C16") (pin "1") (pinfunction "1_1") (pintype "passive"))
      (node (ref "POTE") (pin "13") (pinfunction "W2_13") (pintype "passive"))
      (node (ref "POT_DCOFFSET") (pin "8") (pinfunction "A1_8") (pintype "passive"))
    )
    (net (code "35") (name "/FA3") (class "Default")
      (node (ref "C19") (pin "1") (pinfunction "1_1") (pintype "passive"))
      (node (ref "POTF") (pin "13") (pinfunction "W2_13") (pintype "passive"))
      (node (ref "POTF") (pin "17") (pinfunction "A3_17") (pintype "passive"))
    )
    (net (code "36") (name "/FW1") (class "Default")
      (node (ref "AMP1") (pin "12") (pinfunction "+D_12") (pintype "bidirectional"))
      (node (ref "BPF6GS2TEST") (pin "1") (pinfunction "1_1") (pintype "passive"))
      (node (ref "C18") (pin "1") (pinfunction "1_1") (pintype "passive"))
      (node (ref "POTF") (pin "6") (pinfunction "W1_6") (pintype "passive"))
      (node (ref "POT_DCOFFSET") (pin "13") (pinfunction "W2_13") (pintype "passive"))
    )
    (net (code "37") (name "/GW0") (class "Default")
      (node (ref "AMP2") (pin "3") (pinfunction "+A_3") (pintype "bidirectional"))
      (node (ref "BPF6GS3TEST") (pin "1") (pinfunction "1_1") (pintype "passive"))
      (node (ref "C20") (pin "1") (pinfunction "1_1") (pintype "passive"))
      (node (ref "POTF") (pin "11") (pinfunction "A2_11") (pintype "passive"))
      (node (ref "POT_DCOFFSET") (pin "17") (pinfunction "A3_17") (pintype "passive"))
    )
    (net (code "38") (name "/HPF1IN") (class "Default")
      (node (ref "A2IDEMUX") (pin "15") (pinfunction "A2_15_15") (pintype "bidirectional"))
      (node (ref "AI0DEMUX") (pin "15") (pinfunction "A2_15_15") (pintype "bidirectional"))
      (node (ref "AI1DEMUX") (pin "15") (pinfunction "A2_15_15") (pintype "bidirectional"))
      (node (ref "C7") (pin "2") (pinfunction "2_2") (pintype "passive"))
      (node (ref "HPF1INTEST") (pin "1") (pinfunction "1_1") (pintype "passive"))
    )
    (net (code "39") (name "/HPF1OUT") (class "Default")
      (node (ref "AMP0") (pin "8") (pinfunction "C_8") (pintype "bidirectional"))
      (node (ref "AMP0") (pin "9") (pinfunction "-C_9") (pintype "bidirectional"))
      (node (ref "AO0MUX") (pin "15") (pinfunction "A2_15_15") (pintype "bidirectional"))
      (node (ref "AO1MUX") (pin "15") (pinfunction "A2_15_15") (pintype "bidirectional"))
      (node (ref "AO2MUX") (pin "15") (pinfunction "A2_15_15") (pintype "bidirectional"))
      (node (ref "HPF1OUTTEST") (pin "1") (pinfunction "1_1") (pintype "passive"))
    )
    (net (code "40") (name "/HPF5IN") (class "Default")
      (node (ref "A2IDEMUX") (pin "12") (pinfunction "A3_12_12") (pintype "bidirectional"))
      (node (ref "AI0DEMUX") (pin "12") (pinfunction "A3_12_12") (pintype "bidirectional"))
      (node (ref "AI1DEMUX") (pin "12") (pinfunction "A3_12_12") (pintype "bidirectional"))
      (node (ref "C8") (pin "2") (pinfunction "2_2") (pintype "passive"))
      (node (ref "HPF5INTEST") (pin "1") (pinfunction "1_1") (pintype "passive"))
    )
    (net (code "41") (name "/HPF5OUT") (class "Default")
      (node (ref "AMP0") (pin "13") (pinfunction "-D_13") (pintype "bidirectional"))
      (node (ref "AMP0") (pin "14") (pinfunction "D_14") (pintype "bidirectional"))
      (node (ref "AO0MUX") (pin "12") (pinfunction "A3_12_12") (pintype "bidirectional"))
      (node (ref "AO1MUX") (pin "12") (pinfunction "A3_12_12") (pintype "bidirectional"))
      (node (ref "AO2MUX") (pin "12") (pinfunction "A3_12_12") (pintype "bidirectional"))
      (node (ref "HPF5OUTTEST") (pin "1") (pinfunction "1_1") (pintype "passive"))
    )
    (net (code "42") (name "/I2C1SCL") (class "Default")
      (node (ref "R28") (pin "1") (pinfunction "1_1") (pintype "passive"))
      (node (ref "U$2") (pin "4") (pinfunction "4_4") (pintype "passive"))
      (node (ref "U$4") (pin "17") (pinfunction "PA6_17") (pintype "passive"))
    )
    (net (code "43") (name "/I2C1SDA") (class "Default")
      (node (ref "R29") (pin "1") (pinfunction "1_1") (pintype "passive"))
      (node (ref "U$2") (pin "1") (pinfunction "1_1") (pintype "passive"))
      (node (ref "U$4") (pin "19") (pinfunction "PA7_19") (pintype "passive"))
    )
    (net (code "44") (name "/I2C2SCL") (class "Default")
      (node (ref "R26") (pin "1") (pinfunction "1_1") (pintype "passive"))
      (node (ref "SCLMUX") (pin "3") (pinfunction "COMIN_3_3") (pintype "bidirectional"))
      (node (ref "U$4") (pin "9") (pinfunction "PE4_9") (pintype "passive"))
    )
    (net (code "45") (name "/I2C2SDA") (class "Default")
      (node (ref "POTA") (pin "9") (pinfunction "SDA_9") (pintype "passive"))
      (node (ref "POTB") (pin "9") (pinfunction "SDA_9") (pintype "passive"))
      (node (ref "POTC") (pin "9") (pinfunction "SDA_9") (pintype "passive"))
      (node (ref "POTD") (pin "9") (pinfunction "SDA_9") (pintype "passive"))
      (node (ref "POTE") (pin "9") (pinfunction "SDA_9") (pintype "passive"))
      (node (ref "POTF") (pin "9") (pinfunction "SDA_9") (pintype "passive"))
      (node (ref "POT_DCOFFSET") (pin "9") (pinfunction "SDA_9") (pintype "passive"))
      (node (ref "R27") (pin "1") (pinfunction "1_1") (pintype "passive"))
      (node (ref "U$4") (pin "11") (pinfunction "PE5_11") (pintype "passive"))
    )
    (net (code "46") (name "/LPF1IN") (class "Default")
      (node (ref "A2IDEMUX") (pin "13") (pinfunction "A0_13_13") (pintype "bidirectional"))
      (node (ref "AI0DEMUX") (pin "13") (pinfunction "A0_13_13") (pintype "bidirectional"))
      (node (ref "AI1DEMUX") (pin "13") (pinfunction "A0_13_13") (pintype "bidirectional"))
      (node (ref "LPF1INTEST") (pin "1") (pinfunction "1_1") (pintype "passive"))
      (node (ref "POTA") (pin "3") (pinfunction "A0_3") (pintype "passive"))
    )
    (net (code "47") (name "/LPF1OUT") (class "Default")
      (node (ref "AMP0") (pin "1") (pinfunction "A_1") (pintype "bidirectional"))
      (node (ref "AMP0") (pin "2") (pinfunction "-A_2") (pintype "bidirectional"))
      (node (ref "AO0MUX") (pin "13") (pinfunction "A0_13_13") (pintype "bidirectional"))
      (node (ref "AO1MUX") (pin "13") (pinfunction "A0_13_13") (pintype "bidirectional"))
      (node (ref "AO2MUX") (pin "13") (pinfunction "A0_13_13") (pintype "bidirectional"))
      (node (ref "LPF1OUTTEST") (pin "1") (pinfunction "1_1") (pintype "passive"))
    )
    (net (code "48") (name "/LPF5IN") (class "Default")
      (node (ref "A2IDEMUX") (pin "14") (pinfunction "A1_14_14") (pintype "bidirectional"))
      (node (ref "AI0DEMUX") (pin "14") (pinfunction "A1_14_14") (pintype "bidirectional"))
      (node (ref "AI1DEMUX") (pin "14") (pinfunction "A1_14_14") (pintype "bidirectional"))
      (node (ref "LPF5INTEST") (pin "1") (pinfunction "1_1") (pintype "passive"))
      (node (ref "POTA") (pin "8") (pinfunction "A1_8") (pintype "passive"))
    )
    (net (code "49") (name "/LPF5OUT") (class "Default")
      (node (ref "AMP0") (pin "6") (pinfunction "-B_6") (pintype "bidirectional"))
      (node (ref "AMP0") (pin "7") (pinfunction "B_7") (pintype "bidirectional"))
      (node (ref "AO0MUX") (pin "14") (pinfunction "A1_14_14") (pintype "bidirectional"))
      (node (ref "AO1MUX") (pin "14") (pinfunction "A1_14_14") (pintype "bidirectional"))
      (node (ref "AO2MUX") (pin "14") (pinfunction "A1_14_14") (pintype "bidirectional"))
      (node (ref "LPF5OUTTEST") (pin "1") (pinfunction "1_1") (pintype "passive"))
    )
    (net (code "50") (name "/N$136") (class "Default")
      (node (ref "AMP1") (pin "9") (pinfunction "-C_9") (pintype "bidirectional"))
      (node (ref "R10") (pin "1") (pinfunction "1_1") (pintype "passive"))
      (node (ref "R8") (pin "2") (pinfunction "2_2") (pintype "passive"))
    )
    (net (code "51") (name "/N$140") (class "Default")
      (node (ref "AMP1") (pin "13") (pinfunction "-D_13") (pintype "bidirectional"))
      (node (ref "R11") (pin "1") (pinfunction "1_1") (pintype "passive"))
      (node (ref "R9") (pin "1") (pinfunction "1_1") (pintype "passive"))
    )
    (net (code "52") (name "/NCPOT") (class "Default")
      (node (ref "R15") (pin "2") (pinfunction "2_2") (pintype "passive"))
      (node (ref "SCLMUX") (pin "4") (pinfunction "A7_4_4") (pintype "bidirectional"))
    )
    (net (code "53") (name "/NODEA") (class "Default")
      (node (ref "AMP0") (pin "10") (pinfunction "+C_10") (pintype "bidirectional"))
      (node (ref "C7") (pin "1") (pinfunction "1_1") (pintype "passive"))
      (node (ref "HPF1PREAMPTEST") (pin "1") (pinfunction "1_1") (pintype "passive"))
      (node (ref "POTB") (pin "11") (pinfunction "A2_11") (pintype "passive"))
      (node (ref "POTB") (pin "17") (pinfunction "A3_17") (pintype "passive"))
    )
    (net (code "54") (name "/NODEB") (class "Default")
      (node (ref "AMP0") (pin "12") (pinfunction "+D_12") (pintype "bidirectional"))
      (node (ref "C12") (pin "1") (pinfunction "1_1") (pintype "passive"))
      (node (ref "HPF5PREAMPTEST") (pin "1") (pinfunction "1_1") (pintype "passive"))
      (node (ref "POTD") (pin "3") (pinfunction "A0_3") (pintype "passive"))
      (node (ref "POTD") (pin "8") (pinfunction "A1_8") (pintype "passive"))
    )
    (net (code "55") (name "/NODEC") (class "Default")
      (node (ref "C13") (pin "1") (pinfunction "1_1") (pintype "passive"))
      (node (ref "POTD") (pin "11") (pinfunction "A2_11") (pintype "passive"))
      (node (ref "POTD") (pin "17") (pinfunction "A3_17") (pintype "passive"))
    )
    (net (code "56") (name "/NODED") (class "Default")
      (node (ref "C17") (pin "1") (pinfunction "1_1") (pintype "passive"))
      (node (ref "POTF") (pin "3") (pinfunction "A0_3") (pintype "passive"))
      (node (ref "POTF") (pin "8") (pinfunction "A1_8") (pintype "passive"))
    )
    (net (code "57") (name "/NODEE") (class "Default")
      (node (ref "60HZPREAMPTEST") (pin "1") (pinfunction "1_1") (pintype "passive"))
      (node (ref "AMP2") (pin "10") (pinfunction "+C_10") (pintype "bidirectional"))
      (node (ref "C22") (pin "1") (pinfunction "1_1") (pintype "passive"))
      (node (ref "R24") (pin "2") (pinfunction "2_2") (pintype "passive"))
    )
    (net (code "58") (name "/NODEF") (class "Default")
      (node (ref "C23") (pin "1") (pinfunction "1_1") (pintype "passive"))
      (node (ref "R23") (pin "2") (pinfunction "2_2") (pintype "passive"))
      (node (ref "R24") (pin "1") (pinfunction "1_1") (pintype "passive"))
    )
    (net (code "59") (name "/NODEG") (class "Default")
      (node (ref "C21") (pin "1") (pinfunction "1_1") (pintype "passive"))
      (node (ref "C22") (pin "2") (pinfunction "2_2") (pintype "passive"))
      (node (ref "R25") (pin "1") (pinfunction "1_1") (pintype "passive"))
    )
    (net (code "60") (name "/PASSTHRUIN") (class "Default")
      (node (ref "A2IDEMUX") (pin "4") (pinfunction "A7_4_4") (pintype "bidirectional"))
      (node (ref "AI0DEMUX") (pin "4") (pinfunction "A7_4_4") (pintype "bidirectional"))
      (node (ref "AI1DEMUX") (pin "4") (pinfunction "A7_4_4") (pintype "bidirectional"))
      (node (ref "AMP2") (pin "12") (pinfunction "+D_12") (pintype "bidirectional"))
      (node (ref "PASSTHRUTEST") (pin "1") (pinfunction "1_1") (pintype "passive"))
    )
    (net (code "61") (name "/PASSTHRUOUT") (class "Default")
      (node (ref "AMP2") (pin "13") (pinfunction "-D_13") (pintype "bidirectional"))
      (node (ref "AMP2") (pin "14") (pinfunction "D_14") (pintype "bidirectional"))
      (node (ref "AO0MUX") (pin "4") (pinfunction "A7_4_4") (pintype "bidirectional"))
      (node (ref "AO1MUX") (pin "4") (pinfunction "A7_4_4") (pintype "bidirectional"))
      (node (ref "AO2MUX") (pin "4") (pinfunction "A7_4_4") (pintype "bidirectional"))
    )
    (net (code "62") (name "/S0INPUT") (class "Default")
      (node (ref "AI0DEMUX") (pin "3") (pinfunction "COMIN_3_3") (pintype "bidirectional"))
      (node (ref "S0INPUT") (pin "3") (pinfunction "3_3") (pintype "passive"))
      (node (ref "SENSOR0INPUT") (pin "1") (pinfunction "1_1") (pintype "passive"))
    )
    (net (code "63") (name "/S1INPUT") (class "Default")
      (node (ref "AI1DEMUX") (pin "3") (pinfunction "COMIN_3_3") (pintype "bidirectional"))
      (node (ref "S1INPUT") (pin "3") (pinfunction "3_3") (pintype "passive"))
      (node (ref "SENSOR1INPUT") (pin "1") (pinfunction "1_1") (pintype "passive"))
    )
    (net (code "64") (name "/S2INPUT") (class "Default")
      (node (ref "A2IDEMUX") (pin "3") (pinfunction "COMIN_3_3") (pintype "bidirectional"))
      (node (ref "S2INPUT") (pin "3") (pinfunction "3_3") (pintype "passive"))
      (node (ref "SENSOR2INPUT") (pin "1") (pinfunction "1_1") (pintype "passive"))
    )
    (net (code "65") (name "/SCLA") (class "Default")
      (node (ref "POTA") (pin "14") (pinfunction "SCL_14") (pintype "passive"))
      (node (ref "R22") (pin "2") (pinfunction "2_2") (pintype "passive"))
      (node (ref "SCLMUX") (pin "13") (pinfunction "A0_13_13") (pintype "bidirectional"))
    )
    (net (code "66") (name "/SCLB") (class "Default")
      (node (ref "POTB") (pin "14") (pinfunction "SCL_14") (pintype "passive"))
      (node (ref "R21") (pin "2") (pinfunction "2_2") (pintype "passive"))
      (node (ref "SCLMUX") (pin "14") (pinfunction "A1_14_14") (pintype "bidirectional"))
    )
    (net (code "67") (name "/SCLC") (class "Default")
      (node (ref "POTC") (pin "14") (pinfunction "SCL_14") (pintype "passive"))
      (node (ref "R20") (pin "2") (pinfunction "2_2") (pintype "passive"))
      (node (ref "SCLMUX") (pin "15") (pinfunction "A2_15_15") (pintype "bidirectional"))
    )
    (net (code "68") (name "/SCLD") (class "Default")
      (node (ref "POTD") (pin "14") (pinfunction "SCL_14") (pintype "passive"))
      (node (ref "R19") (pin "2") (pinfunction "2_2") (pintype "passive"))
      (node (ref "SCLMUX") (pin "12") (pinfunction "A3_12_12") (pintype "bidirectional"))
    )
    (net (code "69") (name "/SCLE") (class "Default")
      (node (ref "POTE") (pin "14") (pinfunction "SCL_14") (pintype "passive"))
      (node (ref "R18") (pin "2") (pinfunction "2_2") (pintype "passive"))
      (node (ref "SCLMUX") (pin "1") (pinfunction "A4_1_1") (pintype "bidirectional"))
    )
    (net (code "70") (name "/SCLF") (class "Default")
      (node (ref "POTF") (pin "14") (pinfunction "SCL_14") (pintype "passive"))
      (node (ref "R17") (pin "2") (pinfunction "2_2") (pintype "passive"))
      (node (ref "SCLMUX") (pin "5") (pinfunction "A5_5_5") (pintype "bidirectional"))
    )
    (net (code "71") (name "/SCLG") (class "Default")
      (node (ref "POT_DCOFFSET") (pin "14") (pinfunction "SCL_14") (pintype "passive"))
      (node (ref "R16") (pin "2") (pinfunction "2_2") (pintype "passive"))
      (node (ref "SCLMUX") (pin "2") (pinfunction "A6_2_2") (pintype "bidirectional"))
    )
    (net (code "72") (name "/SCLS0") (class "Default")
      (node (ref "SCLMUX") (pin "11") (pinfunction "S0_11_11") (pintype "bidirectional"))
      (node (ref "U$4") (pin "27") (pinfunction "PC4_27") (pintype "passive"))
    )
    (net (code "73") (name "/SCLS1") (class "Default")
      (node (ref "SCLMUX") (pin "10") (pinfunction "S1_10_10") (pintype "bidirectional"))
      (node (ref "U$4") (pin "29") (pinfunction "PC5_29") (pintype "passive"))
    )
    (net (code "74") (name "/SCLS2") (class "Default")
      (node (ref "SCLMUX") (pin "9") (pinfunction "S2_9_9") (pintype "bidirectional"))
      (node (ref "U$4") (pin "31") (pinfunction "PC6_31") (pintype "passive"))
    )
    (net (code "75") (name "/SSIOCLK") (class "Default")
      (node (ref "U$1") (pin "1") (pinfunction "1_1") (pintype "passive"))
      (node (ref "U$4") (pin "40") (pinfunction "PA2_40") (pintype "passive"))
    )
    (net (code "76") (name "/SSIOFSS") (class "Default")
      (node (ref "U$1") (pin "5") (pinfunction "5_5") (pintype "passive"))
      (node (ref "U$4") (pin "38") (pinfunction "PA3_38") (pintype "passive"))
    )
    (net (code "77") (name "/SSIORX") (class "Default")
      (node (ref "U$1") (pin "3") (pinfunction "3_3") (pintype "passive"))
      (node (ref "U$4") (pin "36") (pinfunction "PA4_36") (pintype "passive"))
    )
    (net (code "78") (name "/SSIOTX") (class "Default")
      (node (ref "U$1") (pin "2") (pinfunction "2_2") (pintype "passive"))
      (node (ref "U$4") (pin "15") (pinfunction "PA5_15") (pintype "passive"))
    )
    (net (code "79") (name "/STAGE1OUT") (class "Default")
      (node (ref "AMP1") (pin "8") (pinfunction "C_8") (pintype "bidirectional"))
      (node (ref "C17") (pin "2") (pinfunction "2_2") (pintype "passive"))
      (node (ref "R8") (pin "1") (pinfunction "1_1") (pintype "passive"))
    )
    (net (code "80") (name "/STAGE2OUT") (class "Default")
      (node (ref "AMP1") (pin "14") (pinfunction "D_14") (pintype "bidirectional"))
      (node (ref "C19") (pin "2") (pinfunction "2_2") (pintype "passive"))
      (node (ref "R9") (pin "2") (pinfunction "2_2") (pintype "passive"))
    )
    (net (code "81") (name "GND") (class "Default")
      (node (ref "A2IDEMUX") (pin "6") (pinfunction "E_6_6") (pintype "bidirectional"))
      (node (ref "A2IDEMUX") (pin "7") (pinfunction "VEE_7_7") (pintype "bidirectional"))
      (node (ref "A2IDEMUX") (pin "8") (pinfunction "GND_8_8") (pintype "bidirectional"))
      (node (ref "AI0DEMUX") (pin "6") (pinfunction "E_6_6") (pintype "bidirectional"))
      (node (ref "AI0DEMUX") (pin "7") (pinfunction "VEE_7_7") (pintype "bidirectional"))
      (node (ref "AI0DEMUX") (pin "8") (pinfunction "GND_8_8") (pintype "bidirectional"))
      (node (ref "AI1DEMUX") (pin "6") (pinfunction "E_6_6") (pintype "bidirectional"))
      (node (ref "AI1DEMUX") (pin "7") (pinfunction "VEE_7_7") (pintype "bidirectional"))
      (node (ref "AI1DEMUX") (pin "8") (pinfunction "GND_8_8") (pintype "bidirectional"))
      (node (ref "AMP0") (pin "11") (pinfunction "-V_11") (pintype "bidirectional"))
      (node (ref "AMP1") (pin "11") (pinfunction "-V_11") (pintype "bidirectional"))
      (node (ref "AMP2") (pin "11") (pinfunction "-V_11") (pintype "bidirectional"))
      (node (ref "AO0MUX") (pin "6") (pinfunction "E_6_6") (pintype "bidirectional"))
      (node (ref "AO0MUX") (pin "7") (pinfunction "VEE_7_7") (pintype "bidirectional"))
      (node (ref "AO0MUX") (pin "8") (pinfunction "GND_8_8") (pintype "bidirectional"))
      (node (ref "AO1MUX") (pin "6") (pinfunction "E_6_6") (pintype "bidirectional"))
      (node (ref "AO1MUX") (pin "7") (pinfunction "VEE_7_7") (pintype "bidirectional"))
      (node (ref "AO1MUX") (pin "8") (pinfunction "GND_8_8") (pintype "bidirectional"))
      (node (ref "AO2MUX") (pin "6") (pinfunction "E_6_6") (pintype "bidirectional"))
      (node (ref "AO2MUX") (pin "7") (pinfunction "VEE_7_7") (pintype "bidirectional"))
      (node (ref "AO2MUX") (pin "8") (pinfunction "GND_8_8") (pintype "bidirectional"))
      (node (ref "C1") (pin "2") (pinfunction "2_2") (pintype "passive"))
      (node (ref "C14") (pin "2") (pinfunction "2_2") (pintype "passive"))
      (node (ref "C16") (pin "2") (pinfunction "2_2") (pintype "passive"))
      (node (ref "C18") (pin "2") (pinfunction "2_2") (pintype "passive"))
      (node (ref "C2") (pin "2") (pinfunction "2_2") (pintype "passive"))
      (node (ref "C20") (pin "2") (pinfunction "2_2") (pintype "passive"))
      (node (ref "C23") (pin "2") (pinfunction "2_2") (pintype "passive"))
      (node (ref "C3") (pin "2") (pinfunction "2_2") (pintype "passive"))
      (node (ref "C4") (pin "2") (pinfunction "2_2") (pintype "passive"))
      (node (ref "C5") (pin "2") (pinfunction "2_2") (pintype "passive"))
      (node (ref "C6") (pin "2") (pinfunction "2_2") (pintype "passive"))
      (node (ref "D1") (pin "C") (pinfunction "C_C") (pintype "passive"))
      (node (ref "POTA") (pin "10") (pinfunction "VSS_10") (pintype "power_in"))
      (node (ref "POTA") (pin "15") (pinfunction "DGND_15") (pintype "passive"))
      (node (ref "POTA") (pin "16") (pinfunction "AD1_16") (pintype "passive"))
      (node (ref "POTA") (pin "4") (pinfunction "AD0_4") (pintype "passive"))
      (node (ref "POTB") (pin "10") (pinfunction "VSS_10") (pintype "power_in"))
      (node (ref "POTB") (pin "15") (pinfunction "DGND_15") (pintype "passive"))
      (node (ref "POTB") (pin "16") (pinfunction "AD1_16") (pintype "passive"))
      (node (ref "POTB") (pin "19") (pinfunction "W3_19") (pintype "passive"))
      (node (ref "POTB") (pin "4") (pinfunction "AD0_4") (pintype "passive"))
      (node (ref "POTC") (pin "1") (pinfunction "W0_1") (pintype "passive"))
      (node (ref "POTC") (pin "10") (pinfunction "VSS_10") (pintype "power_in"))
      (node (ref "POTC") (pin "13") (pinfunction "W2_13") (pintype "passive"))
      (node (ref "POTC") (pin "15") (pinfunction "DGND_15") (pintype "passive"))
      (node (ref "POTC") (pin "16") (pinfunction "AD1_16") (pintype "passive"))
      (node (ref "POTC") (pin "19") (pinfunction "W3_19") (pintype "passive"))
      (node (ref "POTC") (pin "4") (pinfunction "AD0_4") (pintype "passive"))
      (node (ref "POTC") (pin "6") (pinfunction "W1_6") (pintype "passive"))
      (node (ref "POTD") (pin "10") (pinfunction "VSS_10") (pintype "power_in"))
      (node (ref "POTD") (pin "15") (pinfunction "DGND_15") (pintype "passive"))
      (node (ref "POTD") (pin "16") (pinfunction "AD1_16") (pintype "passive"))
      (node (ref "POTD") (pin "19") (pinfunction "W3_19") (pintype "passive"))
      (node (ref "POTD") (pin "4") (pinfunction "AD0_4") (pintype "passive"))
      (node (ref "POTD") (pin "6") (pinfunction "W1_6") (pintype "passive"))
      (node (ref "POTE") (pin "10") (pinfunction "VSS_10") (pintype "power_in"))
      (node (ref "POTE") (pin "15") (pinfunction "DGND_15") (pintype "passive"))
      (node (ref "POTE") (pin "16") (pinfunction "AD1_16") (pintype "passive"))
      (node (ref "POTE") (pin "4") (pinfunction "AD0_4") (pintype "passive"))
      (node (ref "POTE") (pin "6") (pinfunction "W1_6") (pintype "passive"))
      (node (ref "POTF") (pin "1") (pinfunction "W0_1") (pintype "passive"))
      (node (ref "POTF") (pin "10") (pinfunction "VSS_10") (pintype "power_in"))
      (node (ref "POTF") (pin "15") (pinfunction "DGND_15") (pintype "passive"))
      (node (ref "POTF") (pin "16") (pinfunction "AD1_16") (pintype "passive"))
      (node (ref "POTF") (pin "19") (pinfunction "W3_19") (pintype "passive"))
      (node (ref "POTF") (pin "4") (pinfunction "AD0_4") (pintype "passive"))
      (node (ref "POT_DCOFFSET") (pin "10") (pinfunction "VSS_10") (pintype "power_in"))
      (node (ref "POT_DCOFFSET") (pin "15") (pinfunction "DGND_15") (pintype "passive"))
      (node (ref "POT_DCOFFSET") (pin "16") (pinfunction "AD1_16") (pintype "passive"))
      (node (ref "POT_DCOFFSET") (pin "4") (pinfunction "AD0_4") (pintype "passive"))
      (node (ref "R10") (pin "2") (pinfunction "2_2") (pintype "passive"))
      (node (ref "R11") (pin "2") (pinfunction "2_2") (pintype "passive"))
      (node (ref "R25") (pin "2") (pinfunction "2_2") (pintype "passive"))
      (node (ref "R30") (pin "1") (pinfunction "1_1") (pintype "passive"))
      (node (ref "R5") (pin "1") (pinfunction "1_1") (pintype "passive"))
      (node (ref "S0INPUT") (pin "2") (pinfunction "2_2") (pintype "passive"))
      (node (ref "S1INPUT") (pin "2") (pinfunction "2_2") (pintype "passive"))
      (node (ref "S2INPUT") (pin "2") (pinfunction "2_2") (pintype "passive"))
      (node (ref "SCLMUX") (pin "6") (pinfunction "E_6_6") (pintype "bidirectional"))
      (node (ref "SCLMUX") (pin "7") (pinfunction "VEE_7_7") (pintype "bidirectional"))
      (node (ref "SCLMUX") (pin "8") (pinfunction "GND_8_8") (pintype "bidirectional"))
      (node (ref "U$1") (pin "6") (pinfunction "6_6") (pintype "passive"))
      (node (ref "U$2") (pin "3") (pinfunction "3_3") (pintype "passive"))
      (node (ref "U$4") (pin "22") (pinfunction "GND1_22") (pintype "passive"))
      (node (ref "U$4") (pin "4") (pinfunction "GND_4") (pintype "passive"))
    )
    (net (code "82") (name "Net-(AMP2-+B)") (class "Default")
      (node (ref "AMP2") (pin "1") (pinfunction "A_1") (pintype "bidirectional"))
      (node (ref "AMP2") (pin "5") (pinfunction "+B_5") (pintype "bidirectional"))
      (node (ref "R12") (pin "1") (pinfunction "1_1") (pintype "passive"))
    )
    (net (code "83") (name "Net-(AMP2--A)") (class "Default")
      (node (ref "AMP2") (pin "2") (pinfunction "-A_2") (pintype "bidirectional"))
      (node (ref "R12") (pin "2") (pinfunction "2_2") (pintype "passive"))
      (node (ref "R30") (pin "2") (pinfunction "2_2") (pintype "passive"))
    )
    (net (code "84") (name "Net-(CL_RES-Pad1)") (class "Default")
      (node (ref "CL_RES") (pin "1") (pinfunction "1_1") (pintype "passive"))
      (node (ref "D1") (pin "A") (pinfunction "A_A") (pintype "passive"))
    )
    (net (code "85") (name "unconnected-(POTA-B0-Pad2)") (class "Default")
      (node (ref "POTA") (pin "2") (pinfunction "B0_2") (pintype "passive"))
    )
    (net (code "86") (name "unconnected-(POTA-B1-Pad7)") (class "Default")
      (node (ref "POTA") (pin "7") (pinfunction "B1_7") (pintype "passive"))
    )
    (net (code "87") (name "unconnected-(POTA-B2-Pad12)") (class "Default")
      (node (ref "POTA") (pin "12") (pinfunction "B2_12") (pintype "passive"))
    )
    (net (code "88") (name "unconnected-(POTA-B3-Pad18)") (class "Default")
      (node (ref "POTA") (pin "18") (pinfunction "B3_18") (pintype "passive"))
    )
    (net (code "89") (name "unconnected-(POTB-B0-Pad2)") (class "Default")
      (node (ref "POTB") (pin "2") (pinfunction "B0_2") (pintype "passive"))
    )
    (net (code "90") (name "unconnected-(POTB-B1-Pad7)") (class "Default")
      (node (ref "POTB") (pin "7") (pinfunction "B1_7") (pintype "passive"))
    )
    (net (code "91") (name "unconnected-(POTB-B2-Pad12)") (class "Default")
      (node (ref "POTB") (pin "12") (pinfunction "B2_12") (pintype "passive"))
    )
    (net (code "92") (name "unconnected-(POTB-B3-Pad18)") (class "Default")
      (node (ref "POTB") (pin "18") (pinfunction "B3_18") (pintype "passive"))
    )
    (net (code "93") (name "unconnected-(POTC-B0-Pad2)") (class "Default")
      (node (ref "POTC") (pin "2") (pinfunction "B0_2") (pintype "passive"))
    )
    (net (code "94") (name "unconnected-(POTC-B1-Pad7)") (class "Default")
      (node (ref "POTC") (pin "7") (pinfunction "B1_7") (pintype "passive"))
    )
    (net (code "95") (name "unconnected-(POTC-B2-Pad12)") (class "Default")
      (node (ref "POTC") (pin "12") (pinfunction "B2_12") (pintype "passive"))
    )
    (net (code "96") (name "unconnected-(POTC-B3-Pad18)") (class "Default")
      (node (ref "POTC") (pin "18") (pinfunction "B3_18") (pintype "passive"))
    )
    (net (code "97") (name "unconnected-(POTD-B0-Pad2)") (class "Default")
      (node (ref "POTD") (pin "2") (pinfunction "B0_2") (pintype "passive"))
    )
    (net (code "98") (name "unconnected-(POTD-B1-Pad7)") (class "Default")
      (node (ref "POTD") (pin "7") (pinfunction "B1_7") (pintype "passive"))
    )
    (net (code "99") (name "unconnected-(POTD-B2-Pad12)") (class "Default")
      (node (ref "POTD") (pin "12") (pinfunction "B2_12") (pintype "passive"))
    )
    (net (code "100") (name "unconnected-(POTD-B3-Pad18)") (class "Default")
      (node (ref "POTD") (pin "18") (pinfunction "B3_18") (pintype "passive"))
    )
    (net (code "101") (name "unconnected-(POTE-A0-Pad3)") (class "Default")
      (node (ref "POTE") (pin "3") (pinfunction "A0_3") (pintype "passive"))
    )
    (net (code "102") (name "unconnected-(POTE-A3-Pad17)") (class "Default")
      (node (ref "POTE") (pin "17") (pinfunction "A3_17") (pintype "passive"))
    )
    (net (code "103") (name "unconnected-(POTE-B0-Pad2)") (class "Default")
      (node (ref "POTE") (pin "2") (pinfunction "B0_2") (pintype "passive"))
    )
    (net (code "104") (name "unconnected-(POTE-B1-Pad7)") (class "Default")
      (node (ref "POTE") (pin "7") (pinfunction "B1_7") (pintype "passive"))
    )
    (net (code "105") (name "unconnected-(POTE-B2-Pad12)") (class "Default")
      (node (ref "POTE") (pin "12") (pinfunction "B2_12") (pintype "passive"))
    )
    (net (code "106") (name "unconnected-(POTE-B3-Pad18)") (class "Default")
      (node (ref "POTE") (pin "18") (pinfunction "B3_18") (pintype "passive"))
    )
    (net (code "107") (name "unconnected-(POTE-W0-Pad1)") (class "Default")
      (node (ref "POTE") (pin "1") (pinfunction "W0_1") (pintype "passive"))
    )
    (net (code "108") (name "unconnected-(POTE-W3-Pad19)") (class "Default")
      (node (ref "POTE") (pin "19") (pinfunction "W3_19") (pintype "passive"))
    )
    (net (code "109") (name "unconnected-(POTF-B0-Pad2)") (class "Default")
      (node (ref "POTF") (pin "2") (pinfunction "B0_2") (pintype "passive"))
    )
    (net (code "110") (name "unconnected-(POTF-B1-Pad7)") (class "Default")
      (node (ref "POTF") (pin "7") (pinfunction "B1_7") (pintype "passive"))
    )
    (net (code "111") (name "unconnected-(POTF-B2-Pad12)") (class "Default")
      (node (ref "POTF") (pin "12") (pinfunction "B2_12") (pintype "passive"))
    )
    (net (code "112") (name "unconnected-(POTF-B3-Pad18)") (class "Default")
      (node (ref "POTF") (pin "18") (pinfunction "B3_18") (pintype "passive"))
    )
    (net (code "113") (name "unconnected-(POT_DCOFFSET-B0-Pad2)") (class "Default")
      (node (ref "POT_DCOFFSET") (pin "2") (pinfunction "B0_2") (pintype "passive"))
    )
    (net (code "114") (name "unconnected-(POT_DCOFFSET-B1-Pad7)") (class "Default")
      (node (ref "POT_DCOFFSET") (pin "7") (pinfunction "B1_7") (pintype "passive"))
    )
    (net (code "115") (name "unconnected-(POT_DCOFFSET-B2-Pad12)") (class "Default")
      (node (ref "POT_DCOFFSET") (pin "12") (pinfunction "B2_12") (pintype "passive"))
    )
    (net (code "116") (name "unconnected-(POT_DCOFFSET-B3-Pad18)") (class "Default")
      (node (ref "POT_DCOFFSET") (pin "18") (pinfunction "B3_18") (pintype "passive"))
    )
    (net (code "117") (name "unconnected-(U$4-PC7-Pad33)") (class "Default")
      (node (ref "U$4") (pin "33") (pinfunction "PC7_33") (pintype "passive"))
    )
    (net (code "118") (name "unconnected-(U$4-PD1-Pad8)") (class "Default")
      (node (ref "U$4") (pin "8") (pinfunction "PD1_8") (pintype "passive"))
    )
    (net (code "119") (name "unconnected-(U$4-PD2-Pad10)") (class "Default")
      (node (ref "U$4") (pin "10") (pinfunction "PD2_10") (pintype "passive"))
    )
    (net (code "120") (name "unconnected-(U$4-PD3-Pad12)") (class "Default")
      (node (ref "U$4") (pin "12") (pinfunction "PD3_12") (pintype "passive"))
    )
    (net (code "121") (name "unconnected-(U$4-PD6-Pad35)") (class "Default")
      (node (ref "U$4") (pin "35") (pinfunction "PD6_35") (pintype "passive"))
    )
    (net (code "122") (name "unconnected-(U$4-PD7-Pad37)") (class "Default")
      (node (ref "U$4") (pin "37") (pinfunction "PD7_37") (pintype "passive"))
    )
    (net (code "123") (name "unconnected-(U$4-PE0-Pad26)") (class "Default")
      (node (ref "U$4") (pin "26") (pinfunction "PE0_26") (pintype "passive"))
    )
    (net (code "124") (name "unconnected-(U$4-PF0-Pad28)") (class "Default")
      (node (ref "U$4") (pin "28") (pinfunction "PF0_28") (pintype "passive"))
    )
    (net (code "125") (name "unconnected-(U$4-PF1-Pad20)") (class "Default")
      (node (ref "U$4") (pin "20") (pinfunction "PF1_20") (pintype "passive"))
    )
    (net (code "126") (name "unconnected-(U$4-PF2-Pad21)") (class "Default")
      (node (ref "U$4") (pin "21") (pinfunction "PF2_21") (pintype "passive"))
    )
    (net (code "127") (name "unconnected-(U$4-PF3-Pad23)") (class "Default")
      (node (ref "U$4") (pin "23") (pinfunction "PF3_23") (pintype "passive"))
    )
    (net (code "128") (name "unconnected-(U$4-PF4-Pad39)") (class "Default")
      (node (ref "U$4") (pin "39") (pinfunction "PF4_39") (pintype "passive"))
    )
    (net (code "129") (name "unconnected-(U$4-RESET-Pad30)") (class "Default")
      (node (ref "U$4") (pin "30") (pinfunction "RESET_30") (pintype "passive"))
    )
    (net (code "130") (name "unconnected-(U$4-VBUS-Pad2)") (class "Default")
      (node (ref "U$4") (pin "2") (pinfunction "VBUS_2") (pintype "passive"))
    )
  )
)
